# AUDIO_CODEC.net
KiCad netlist of a schematic drawn in Altium Designer
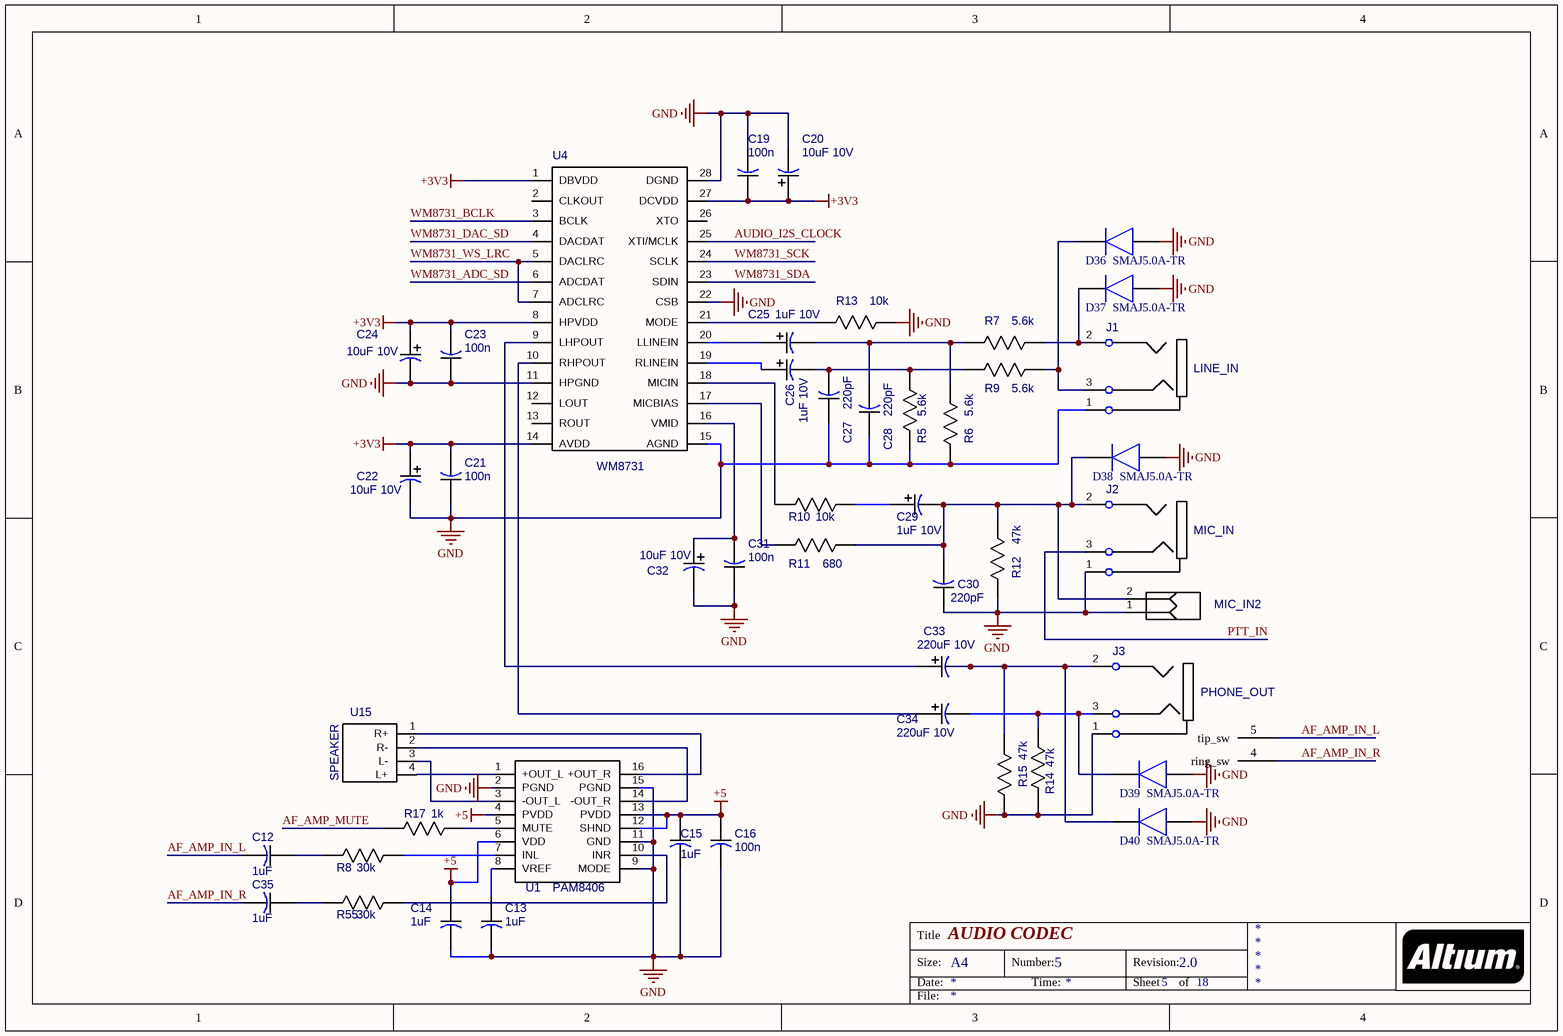
[diagram p0: AUDIO CODEC.SchDoc]

(export (version "E")
  (design (tool "Eeschema 10.0.6"))
  (components
    (comp (ref "C12")
      (value "1uF")
      (footprint "CAP_0805")
      (description "CAP_0805")
      (libsource (lib "*") (part "CAP_0805"))
    )
    (comp (ref "C13")
      (value "1uF")
      (footprint "CAP_0805")
      (description "CAP_0805")
      (libsource (lib "*") (part "CAP_0805"))
    )
    (comp (ref "C14")
      (value "1uF")
      (footprint "CAP_0805")
      (description "CAP_0805")
      (libsource (lib "*") (part "CAP_0805"))
    )
    (comp (ref "C15")
      (value "1uF")
      (footprint "CAP_0805")
      (description "CAP_0805")
      (libsource (lib "*") (part "CAP_0805"))
    )
    (comp (ref "C16")
      (value "100n")
      (footprint "CAP_0805")
      (description "CAP_0805")
      (libsource (lib "*") (part "CAP_0805"))
    )
    (comp (ref "C19")
      (value "100n")
      (footprint "CAP_0805")
      (description "CAP_0805")
      (libsource (lib "*") (part "CAP_0805"))
    )
    (comp (ref "C20")
      (value "10uF 10V")
      (footprint "CAPAE_4.3x4.3h5.4")
      (description "CAPAE_4.3x4.3h5.4")
      (libsource (lib "*") (part "CAPAE_4.3x4.3h5.4"))
    )
    (comp (ref "C21")
      (value "100n")
      (footprint "CAP_0805")
      (description "CAP_0805")
      (libsource (lib "*") (part "CAP_0805"))
    )
    (comp (ref "C22")
      (value "10uF 10V")
      (footprint "CAPAE_4.3x4.3h5.4")
      (description "CAPAE_4.3x4.3h5.4")
      (libsource (lib "*") (part "CAPAE_4.3x4.3h5.4"))
    )
    (comp (ref "C23")
      (value "100n")
      (footprint "CAP_0805")
      (description "CAP_0805")
      (libsource (lib "*") (part "CAP_0805"))
    )
    (comp (ref "C24")
      (value "10uF 10V")
      (footprint "CAPAE_4.3x4.3h5.4")
      (description "CAPAE_4.3x4.3h5.4")
      (libsource (lib "*") (part "CAPAE_4.3x4.3h5.4"))
    )
    (comp (ref "C25")
      (value "1uF 10V")
      (footprint "CAPAE_4.3x4.3h5.4")
      (description "CAPAE_4.3x4.3h5.4")
      (libsource (lib "*") (part "CAPAE_4.3x4.3h5.4"))
    )
    (comp (ref "C26")
      (value "1uF 10V")
      (footprint "CAPAE_4.3x4.3h5.4")
      (description "CAPAE_4.3x4.3h5.4")
      (libsource (lib "*") (part "CAPAE_4.3x4.3h5.4"))
    )
    (comp (ref "C27")
      (value "220pF")
      (footprint "CAP_0805")
      (description "CAP_0805")
      (libsource (lib "*") (part "CAP_0805"))
    )
    (comp (ref "C28")
      (value "220pF")
      (footprint "CAP_0805")
      (description "CAP_0805")
      (libsource (lib "*") (part "CAP_0805"))
    )
    (comp (ref "C29")
      (value "1uF 10V")
      (footprint "CAPAE_4.3x4.3h5.4")
      (description "CAPAE_4.3x4.3h5.4")
      (libsource (lib "*") (part "CAPAE_4.3x4.3h5.4"))
    )
    (comp (ref "C30")
      (value "220pF")
      (footprint "CAP_0805")
      (description "CAP_0805")
      (libsource (lib "*") (part "CAP_0805"))
    )
    (comp (ref "C31")
      (value "100n")
      (footprint "CAP_0805")
      (description "CAP_0805")
      (libsource (lib "*") (part "CAP_0805"))
    )
    (comp (ref "C32")
      (value "10uF 10V")
      (footprint "CAPAE_4.3x4.3h5.4")
      (description "CAPAE_4.3x4.3h5.4")
      (libsource (lib "*") (part "CAPAE_4.3x4.3h5.4"))
    )
    (comp (ref "C33")
      (value "220uF 10V")
      (footprint "EEEFC_sizeС")
      (description "CAPAE_4.3x4.3h5.4")
      (libsource (lib "*") (part "CAPAE_4.3x4.3h5.4"))
    )
    (comp (ref "C34")
      (value "220uF 10V")
      (footprint "EEEFC_sizeС")
      (description "CAPAE_4.3x4.3h5.4")
      (libsource (lib "*") (part "CAPAE_4.3x4.3h5.4"))
    )
    (comp (ref "C35")
      (value "1uF")
      (footprint "CAP_0805")
      (description "CAP_0805")
      (libsource (lib "*") (part "CAP_0805"))
    )
    (comp (ref "D36")
      (value "SMAJ5.0A-TR")
      (footprint "SamacSys:SMBJ36CATR")
      (description "Diode")
      (fields
        (field (name "MANUFACTURER_PART_NUMBER") "SMLVT3V3")
        (field (name "MOUSER PART NUMBER") "511-SMLVT3V3")
      )
      (libsource (lib "*") (part "SMLVT3V3"))
    )
    (comp (ref "D37")
      (value "SMAJ5.0A-TR")
      (footprint "SamacSys:SMBJ36CATR")
      (description "Diode")
      (fields
        (field (name "MANUFACTURER_PART_NUMBER") "SMLVT3V3")
        (field (name "MOUSER PART NUMBER") "511-SMLVT3V3")
      )
      (libsource (lib "*") (part "SMLVT3V3"))
    )
    (comp (ref "D38")
      (value "SMAJ5.0A-TR")
      (footprint "SamacSys:SMBJ36CATR")
      (description "Diode")
      (fields
        (field (name "MANUFACTURER_PART_NUMBER") "SMLVT3V3")
        (field (name "MOUSER PART NUMBER") "511-SMLVT3V3")
      )
      (libsource (lib "*") (part "SMLVT3V3"))
    )
    (comp (ref "D39")
      (value "SMAJ5.0A-TR")
      (footprint "SamacSys:SMBJ36CATR")
      (description "Diode")
      (fields
        (field (name "MANUFACTURER_PART_NUMBER") "SMLVT3V3")
        (field (name "MOUSER PART NUMBER") "511-SMLVT3V3")
      )
      (libsource (lib "*") (part "SMLVT3V3"))
    )
    (comp (ref "D40")
      (value "SMAJ5.0A-TR")
      (footprint "SamacSys:SMBJ36CATR")
      (description "Diode")
      (fields
        (field (name "MANUFACTURER_PART_NUMBER") "SMLVT3V3")
        (field (name "MOUSER PART NUMBER") "511-SMLVT3V3")
      )
      (libsource (lib "*") (part "SMLVT3V3"))
    )
    (comp (ref "J1")
      (value "LINE_IN")
      (footprint "SJ1-3525NG")
      (description "SJ1-3525NG")
      (libsource (lib "") (part "SJ1-3523N_1"))
    )
    (comp (ref "J2")
      (value "MIC_IN")
      (footprint "SJ1-3525NG")
      (description "SJ1-3525NG")
      (libsource (lib "") (part "SJ1-3523N_1"))
    )
    (comp (ref "J3")
      (value "PHONE_OUT")
      (footprint "SJ1-3525NG")
      (description "SJ1-3525NG")
      (libsource (lib "*") (part "SJ1-3523N"))
    )
    (comp (ref "MIС_IN2")
      (value "MIС_IN2")
      (footprint "51022-0200")
      (description "2 Pin")
      (libsource (lib "*") (part "51022-0200"))
    )
    (comp (ref "R5")
      (value "5.6k")
      (footprint "RES_0805")
      (description "RES_0805")
      (libsource (lib "*") (part "RES_0805"))
    )
    (comp (ref "R6")
      (value "5.6k")
      (footprint "RES_0805")
      (description "RES_0805")
      (libsource (lib "*") (part "RES_0805"))
    )
    (comp (ref "R7")
      (value "5.6k")
      (footprint "RES_0805")
      (description "RES_0805")
      (libsource (lib "*") (part "RES_0805"))
    )
    (comp (ref "R8")
      (value "30k")
      (footprint "RES_0805")
      (description "RES_0805")
      (libsource (lib "*") (part "RES_0805"))
    )
    (comp (ref "R9")
      (value "5.6k")
      (footprint "RES_0805")
      (description "RES_0805")
      (libsource (lib "*") (part "RES_0805"))
    )
    (comp (ref "R10")
      (value "10k")
      (footprint "RES_0805")
      (description "RES_0805")
      (libsource (lib "*") (part "RES_0805"))
    )
    (comp (ref "R11")
      (value "680")
      (footprint "RES_0805")
      (description "RES_0805")
      (libsource (lib "*") (part "RES_0805"))
    )
    (comp (ref "R12")
      (value "47k")
      (footprint "RES_0805")
      (description "RES_0805")
      (libsource (lib "*") (part "RES_0805"))
    )
    (comp (ref "R13")
      (value "10k")
      (footprint "RES_0805")
      (description "RES_0805")
      (libsource (lib "*") (part "RES_0805"))
    )
    (comp (ref "R14")
      (value "47k")
      (footprint "RES_0805")
      (description "RES_0805")
      (libsource (lib "*") (part "RES_0805"))
    )
    (comp (ref "R15")
      (value "47k")
      (footprint "RES_0805")
      (description "RES_0805")
      (libsource (lib "*") (part "RES_0805"))
    )
    (comp (ref "R17")
      (value "1k")
      (footprint "RES_0805")
      (description "RES_0805")
      (libsource (lib "*") (part "RES_0805"))
    )
    (comp (ref "R55")
      (value "30k")
      (footprint "RES_0805")
      (description "RES_0805")
      (libsource (lib "*") (part "RES_0805"))
    )
    (comp (ref "U1")
      (value "PAM8406")
      (footprint "SOP-16/7x1.27")
      (libsource (lib "MOTHERBOARD") (part "PAM8406"))
    )
    (comp (ref "U4") (value "WM8731") (footprint "WM8731") (libsource (lib "*") (part "WM8731")))
    (comp (ref "U15")
      (value "SPEAKER")
      (footprint "speaker conn")
      (description "4 pins conn")
      (libsource (lib "MOTHERBOARD") (part "speaker conn"))
    )
  )
  (nets
    (net (code "1") (name "+3V3") (class "Default")
      (node (ref "C19") (pin "1") (pinfunction "1_1") (pintype "passive"))
      (node (ref "C20") (pin "1") (pinfunction "PLUS_1") (pintype "passive"))
      (node (ref "C21") (pin "2") (pinfunction "2_2") (pintype "passive"))
      (node (ref "C22") (pin "1") (pinfunction "PLUS_1") (pintype "passive"))
      (node (ref "C23") (pin "2") (pinfunction "2_2") (pintype "passive"))
      (node (ref "C24") (pin "1") (pinfunction "PLUS_1") (pintype "passive"))
      (node (ref "U4") (pin "1") (pinfunction "DBVDD_1") (pintype "passive"))
      (node (ref "U4") (pin "14") (pinfunction "AVDD_14") (pintype "passive"))
      (node (ref "U4") (pin "27") (pinfunction "DCVDD_27") (pintype "passive"))
      (node (ref "U4") (pin "8") (pinfunction "HPVDD_8") (pintype "passive"))
    )
    (net (code "2") (name "+5") (class "Default")
      (node (ref "C14") (pin "1") (pinfunction "1_1") (pintype "passive"))
      (node (ref "C15") (pin "1") (pinfunction "1_1") (pintype "passive"))
      (node (ref "C16") (pin "1") (pinfunction "1_1") (pintype "passive"))
      (node (ref "U1") (pin "12") (pinfunction "SHND_12") (pintype "passive"))
      (node (ref "U1") (pin "13") (pinfunction "PVDD_13") (pintype "passive"))
      (node (ref "U1") (pin "4") (pinfunction "PVDD_4") (pintype "passive"))
      (node (ref "U1") (pin "6") (pinfunction "VDD_6") (pintype "passive"))
    )
    (net (code "3") (name "/AF_AMP_IN_L") (class "Default")
      (node (ref "C12") (pin "2") (pinfunction "2_2") (pintype "passive"))
      (node (ref "J3") (pin "5") (pinfunction "tip_sw_5") (pintype "passive"))
    )
    (net (code "4") (name "/AF_AMP_IN_R") (class "Default")
      (node (ref "C35") (pin "2") (pinfunction "2_2") (pintype "passive"))
      (node (ref "J3") (pin "4") (pinfunction "ring_sw_4") (pintype "passive"))
    )
    (net (code "5") (name "/AF_AMP_MUTE") (class "Default")
      (node (ref "R17") (pin "2") (pinfunction "2_2") (pintype "passive"))
    )
    (net (code "6") (name "/AUDIO_I2S_CLOCK") (class "Default")
      (node (ref "U4") (pin "25") (pinfunction "XTI/MCLK_25") (pintype "passive"))
    )
    (net (code "7") (name "/PTT_IN") (class "Default")
      (node (ref "J2") (pin "3") (pinfunction "ring_3") (pintype "passive"))
    )
    (net (code "8") (name "/WM8731_ADC_SD") (class "Default")
      (node (ref "U4") (pin "6") (pinfunction "ADCDAT_6") (pintype "passive"))
    )
    (net (code "9") (name "/WM8731_BCLK") (class "Default")
      (node (ref "U4") (pin "3") (pinfunction "BCLK_3") (pintype "passive"))
    )
    (net (code "10") (name "/WM8731_DAC_SD") (class "Default")
      (node (ref "U4") (pin "4") (pinfunction "DACDAT_4") (pintype "passive"))
    )
    (net (code "11") (name "/WM8731_SCK") (class "Default")
      (node (ref "U4") (pin "24") (pinfunction "SCLK_24") (pintype "passive"))
    )
    (net (code "12") (name "/WM8731_SDA") (class "Default")
      (node (ref "U4") (pin "23") (pinfunction "SDIN_23") (pintype "passive"))
    )
    (net (code "13") (name "/WM8731_WS_LRC") (class "Default")
      (node (ref "U4") (pin "5") (pinfunction "DACLRC_5") (pintype "passive"))
      (node (ref "U4") (pin "7") (pinfunction "ADCLRC_7") (pintype "passive"))
    )
    (net (code "14") (name "GND") (class "Default")
      (node (ref "C13") (pin "2") (pinfunction "2_2") (pintype "passive"))
      (node (ref "C14") (pin "2") (pinfunction "2_2") (pintype "passive"))
      (node (ref "C15") (pin "2") (pinfunction "2_2") (pintype "passive"))
      (node (ref "C16") (pin "2") (pinfunction "2_2") (pintype "passive"))
      (node (ref "C19") (pin "2") (pinfunction "2_2") (pintype "passive"))
      (node (ref "C20") (pin "2") (pinfunction "MINUS_2") (pintype "passive"))
      (node (ref "C21") (pin "1") (pinfunction "1_1") (pintype "passive"))
      (node (ref "C22") (pin "2") (pinfunction "MINUS_2") (pintype "passive"))
      (node (ref "C23") (pin "1") (pinfunction "1_1") (pintype "passive"))
      (node (ref "C24") (pin "2") (pinfunction "MINUS_2") (pintype "passive"))
      (node (ref "C27") (pin "1") (pinfunction "1_1") (pintype "passive"))
      (node (ref "C28") (pin "1") (pinfunction "1_1") (pintype "passive"))
      (node (ref "C30") (pin "1") (pinfunction "1_1") (pintype "passive"))
      (node (ref "C31") (pin "1") (pinfunction "1_1") (pintype "passive"))
      (node (ref "C32") (pin "2") (pinfunction "MINUS_2") (pintype "passive"))
      (node (ref "D36") (pin "2") (pinfunction "A_2") (pintype "passive"))
      (node (ref "D37") (pin "2") (pinfunction "A_2") (pintype "passive"))
      (node (ref "D38") (pin "2") (pinfunction "A_2") (pintype "passive"))
      (node (ref "D39") (pin "2") (pinfunction "A_2") (pintype "passive"))
      (node (ref "D40") (pin "2") (pinfunction "A_2") (pintype "passive"))
      (node (ref "J1") (pin "1") (pinfunction "sleeve_1") (pintype "passive"))
      (node (ref "J2") (pin "1") (pinfunction "sleeve_1") (pintype "passive"))
      (node (ref "J3") (pin "1") (pinfunction "sleeve_1") (pintype "passive"))
      (node (ref "MIС_IN2") (pin "1") (pinfunction "1_1") (pintype "passive"))
      (node (ref "R12") (pin "1") (pinfunction "1_1") (pintype "passive"))
      (node (ref "R13") (pin "1") (pinfunction "1_1") (pintype "passive"))
      (node (ref "R14") (pin "1") (pinfunction "1_1") (pintype "passive"))
      (node (ref "R15") (pin "1") (pinfunction "1_1") (pintype "passive"))
      (node (ref "R5") (pin "1") (pinfunction "1_1") (pintype "passive"))
      (node (ref "R6") (pin "1") (pinfunction "1_1") (pintype "passive"))
      (node (ref "U1") (pin "11") (pinfunction "GND_11") (pintype "passive"))
      (node (ref "U1") (pin "15") (pinfunction "PGND_15") (pintype "passive"))
      (node (ref "U1") (pin "2") (pinfunction "PGND_2") (pintype "passive"))
      (node (ref "U1") (pin "9") (pinfunction "MODE_9") (pintype "passive"))
      (node (ref "U4") (pin "11") (pinfunction "HPGND_11") (pintype "passive"))
      (node (ref "U4") (pin "15") (pinfunction "AGND_15") (pintype "passive"))
      (node (ref "U4") (pin "22") (pinfunction "CSB_22") (pintype "passive"))
      (node (ref "U4") (pin "28") (pinfunction "DGND_28") (pintype "passive"))
    )
    (net (code "15") (name "Net-(C12-Pad1)") (class "Default")
      (node (ref "C12") (pin "1") (pinfunction "1_1") (pintype "passive"))
      (node (ref "R8") (pin "2") (pinfunction "2_2") (pintype "passive"))
    )
    (net (code "16") (name "Net-(C25-MINUS)") (class "Default")
      (node (ref "C25") (pin "2") (pinfunction "MINUS_2") (pintype "passive"))
      (node (ref "C28") (pin "2") (pinfunction "2_2") (pintype "passive"))
      (node (ref "R6") (pin "2") (pinfunction "2_2") (pintype "passive"))
      (node (ref "R7") (pin "2") (pinfunction "2_2") (pintype "passive"))
    )
    (net (code "17") (name "Net-(C25-PLUS)") (class "Default")
      (node (ref "C25") (pin "1") (pinfunction "PLUS_1") (pintype "passive"))
      (node (ref "U4") (pin "20") (pinfunction "LLINEIN_20") (pintype "passive"))
    )
    (net (code "18") (name "Net-(C26-MINUS)") (class "Default")
      (node (ref "C26") (pin "2") (pinfunction "MINUS_2") (pintype "passive"))
      (node (ref "C27") (pin "2") (pinfunction "2_2") (pintype "passive"))
      (node (ref "R5") (pin "2") (pinfunction "2_2") (pintype "passive"))
      (node (ref "R9") (pin "2") (pinfunction "2_2") (pintype "passive"))
    )
    (net (code "19") (name "Net-(C26-PLUS)") (class "Default")
      (node (ref "C26") (pin "1") (pinfunction "PLUS_1") (pintype "passive"))
      (node (ref "U4") (pin "19") (pinfunction "RLINEIN_19") (pintype "passive"))
    )
    (net (code "20") (name "Net-(C29-MINUS)") (class "Default")
      (node (ref "C29") (pin "2") (pinfunction "MINUS_2") (pintype "passive"))
      (node (ref "C30") (pin "2") (pinfunction "2_2") (pintype "passive"))
      (node (ref "D38") (pin "1") (pinfunction "K_1") (pintype "passive"))
      (node (ref "J2") (pin "2") (pinfunction "tip_2") (pintype "passive"))
      (node (ref "MIС_IN2") (pin "2") (pinfunction "2_2") (pintype "passive"))
      (node (ref "R11") (pin "1") (pinfunction "1_1") (pintype "passive"))
      (node (ref "R12") (pin "2") (pinfunction "2_2") (pintype "passive"))
    )
    (net (code "21") (name "Net-(C29-PLUS)") (class "Default")
      (node (ref "C29") (pin "1") (pinfunction "PLUS_1") (pintype "passive"))
      (node (ref "R10") (pin "1") (pinfunction "1_1") (pintype "passive"))
    )
    (net (code "22") (name "Net-(C32-PLUS)") (class "Default")
      (node (ref "C31") (pin "2") (pinfunction "2_2") (pintype "passive"))
      (node (ref "C32") (pin "1") (pinfunction "PLUS_1") (pintype "passive"))
      (node (ref "U4") (pin "16") (pinfunction "VMID_16") (pintype "passive"))
    )
    (net (code "23") (name "Net-(C33-MINUS)") (class "Default")
      (node (ref "C33") (pin "2") (pinfunction "MINUS_2") (pintype "passive"))
      (node (ref "D40") (pin "1") (pinfunction "K_1") (pintype "passive"))
      (node (ref "J3") (pin "2") (pinfunction "tip_2") (pintype "passive"))
      (node (ref "R15") (pin "2") (pinfunction "2_2") (pintype "passive"))
    )
    (net (code "24") (name "Net-(C33-PLUS)") (class "Default")
      (node (ref "C33") (pin "1") (pinfunction "PLUS_1") (pintype "passive"))
      (node (ref "U4") (pin "9") (pinfunction "LHPOUT_9") (pintype "passive"))
    )
    (net (code "25") (name "Net-(C34-MINUS)") (class "Default")
      (node (ref "C34") (pin "2") (pinfunction "MINUS_2") (pintype "passive"))
      (node (ref "D39") (pin "1") (pinfunction "K_1") (pintype "passive"))
      (node (ref "J3") (pin "3") (pinfunction "ring_3") (pintype "passive"))
      (node (ref "R14") (pin "2") (pinfunction "2_2") (pintype "passive"))
    )
    (net (code "26") (name "Net-(C34-PLUS)") (class "Default")
      (node (ref "C34") (pin "1") (pinfunction "PLUS_1") (pintype "passive"))
      (node (ref "U4") (pin "10") (pinfunction "RHPOUT_10") (pintype "passive"))
    )
    (net (code "27") (name "Net-(C35-Pad1)") (class "Default")
      (node (ref "C35") (pin "1") (pinfunction "1_1") (pintype "passive"))
      (node (ref "R55") (pin "2") (pinfunction "2_2") (pintype "passive"))
    )
    (net (code "28") (name "Net-(D36-K)") (class "Default")
      (node (ref "D36") (pin "1") (pinfunction "K_1") (pintype "passive"))
      (node (ref "J1") (pin "3") (pinfunction "ring_3") (pintype "passive"))
      (node (ref "R9") (pin "1") (pinfunction "1_1") (pintype "passive"))
    )
    (net (code "29") (name "Net-(D37-K)") (class "Default")
      (node (ref "D37") (pin "1") (pinfunction "K_1") (pintype "passive"))
      (node (ref "J1") (pin "2") (pinfunction "tip_2") (pintype "passive"))
      (node (ref "R7") (pin "1") (pinfunction "1_1") (pintype "passive"))
    )
    (net (code "30") (name "Net-(U1-+OUT_L)") (class "Default")
      (node (ref "U1") (pin "1") (pinfunction "+OUT_L_1") (pintype "passive"))
      (node (ref "U15") (pin "4") (pinfunction "L+_4") (pintype "passive"))
    )
    (net (code "31") (name "Net-(U1-+OUT_R)") (class "Default")
      (node (ref "U1") (pin "16") (pinfunction "+OUT_R_16") (pintype "passive"))
      (node (ref "U15") (pin "1") (pinfunction "R+_1") (pintype "passive"))
    )
    (net (code "32") (name "Net-(U1--OUT_L)") (class "Default")
      (node (ref "U1") (pin "3") (pinfunction "-OUT_L_3") (pintype "passive"))
      (node (ref "U15") (pin "3") (pinfunction "L-_3") (pintype "passive"))
    )
    (net (code "33") (name "Net-(U1--OUT_R)") (class "Default")
      (node (ref "U1") (pin "14") (pinfunction "-OUT_R_14") (pintype "passive"))
      (node (ref "U15") (pin "2") (pinfunction "R-_2") (pintype "passive"))
    )
    (net (code "34") (name "Net-(U1-INL)") (class "Default")
      (node (ref "R8") (pin "1") (pinfunction "1_1") (pintype "passive"))
      (node (ref "U1") (pin "7") (pinfunction "INL_7") (pintype "passive"))
    )
    (net (code "35") (name "Net-(U1-INR)") (class "Default")
      (node (ref "R55") (pin "1") (pinfunction "1_1") (pintype "passive"))
      (node (ref "U1") (pin "10") (pinfunction "INR_10") (pintype "passive"))
    )
    (net (code "36") (name "Net-(U1-MUTE)") (class "Default")
      (node (ref "R17") (pin "1") (pinfunction "1_1") (pintype "passive"))
      (node (ref "U1") (pin "5") (pinfunction "MUTE_5") (pintype "passive"))
    )
    (net (code "37") (name "Net-(U1-VREF)") (class "Default")
      (node (ref "C13") (pin "1") (pinfunction "1_1") (pintype "passive"))
      (node (ref "U1") (pin "8") (pinfunction "VREF_8") (pintype "passive"))
    )
    (net (code "38") (name "Net-(U4-MICBIAS)") (class "Default")
      (node (ref "R11") (pin "2") (pinfunction "2_2") (pintype "passive"))
      (node (ref "U4") (pin "17") (pinfunction "MICBIAS_17") (pintype "passive"))
    )
    (net (code "39") (name "Net-(U4-MICIN)") (class "Default")
      (node (ref "R10") (pin "2") (pinfunction "2_2") (pintype "passive"))
      (node (ref "U4") (pin "18") (pinfunction "MICIN_18") (pintype "passive"))
    )
    (net (code "40") (name "Net-(U4-MODE)") (class "Default")
      (node (ref "R13") (pin "2") (pinfunction "2_2") (pintype "passive"))
      (node (ref "U4") (pin "21") (pinfunction "MODE_21") (pintype "passive"))
    )
    (net (code "41") (name "unconnected-(U4-CLKOUT-Pad2)") (class "Default")
      (node (ref "U4") (pin "2") (pinfunction "CLKOUT_2") (pintype "passive"))
    )
    (net (code "42") (name "unconnected-(U4-LOUT-Pad12)") (class "Default")
      (node (ref "U4") (pin "12") (pinfunction "LOUT_12") (pintype "passive"))
    )
    (net (code "43") (name "unconnected-(U4-ROUT-Pad13)") (class "Default")
      (node (ref "U4") (pin "13") (pinfunction "ROUT_13") (pintype "passive"))
    )
    (net (code "44") (name "unconnected-(U4-XTO-Pad26)") (class "Default")
      (node (ref "U4") (pin "26") (pinfunction "XTO_26") (pintype "passive"))
    )
  )
)
